# Photodiode_TIA_real_comp.net
KiCad netlist of a schematic drawn in Altium Designer
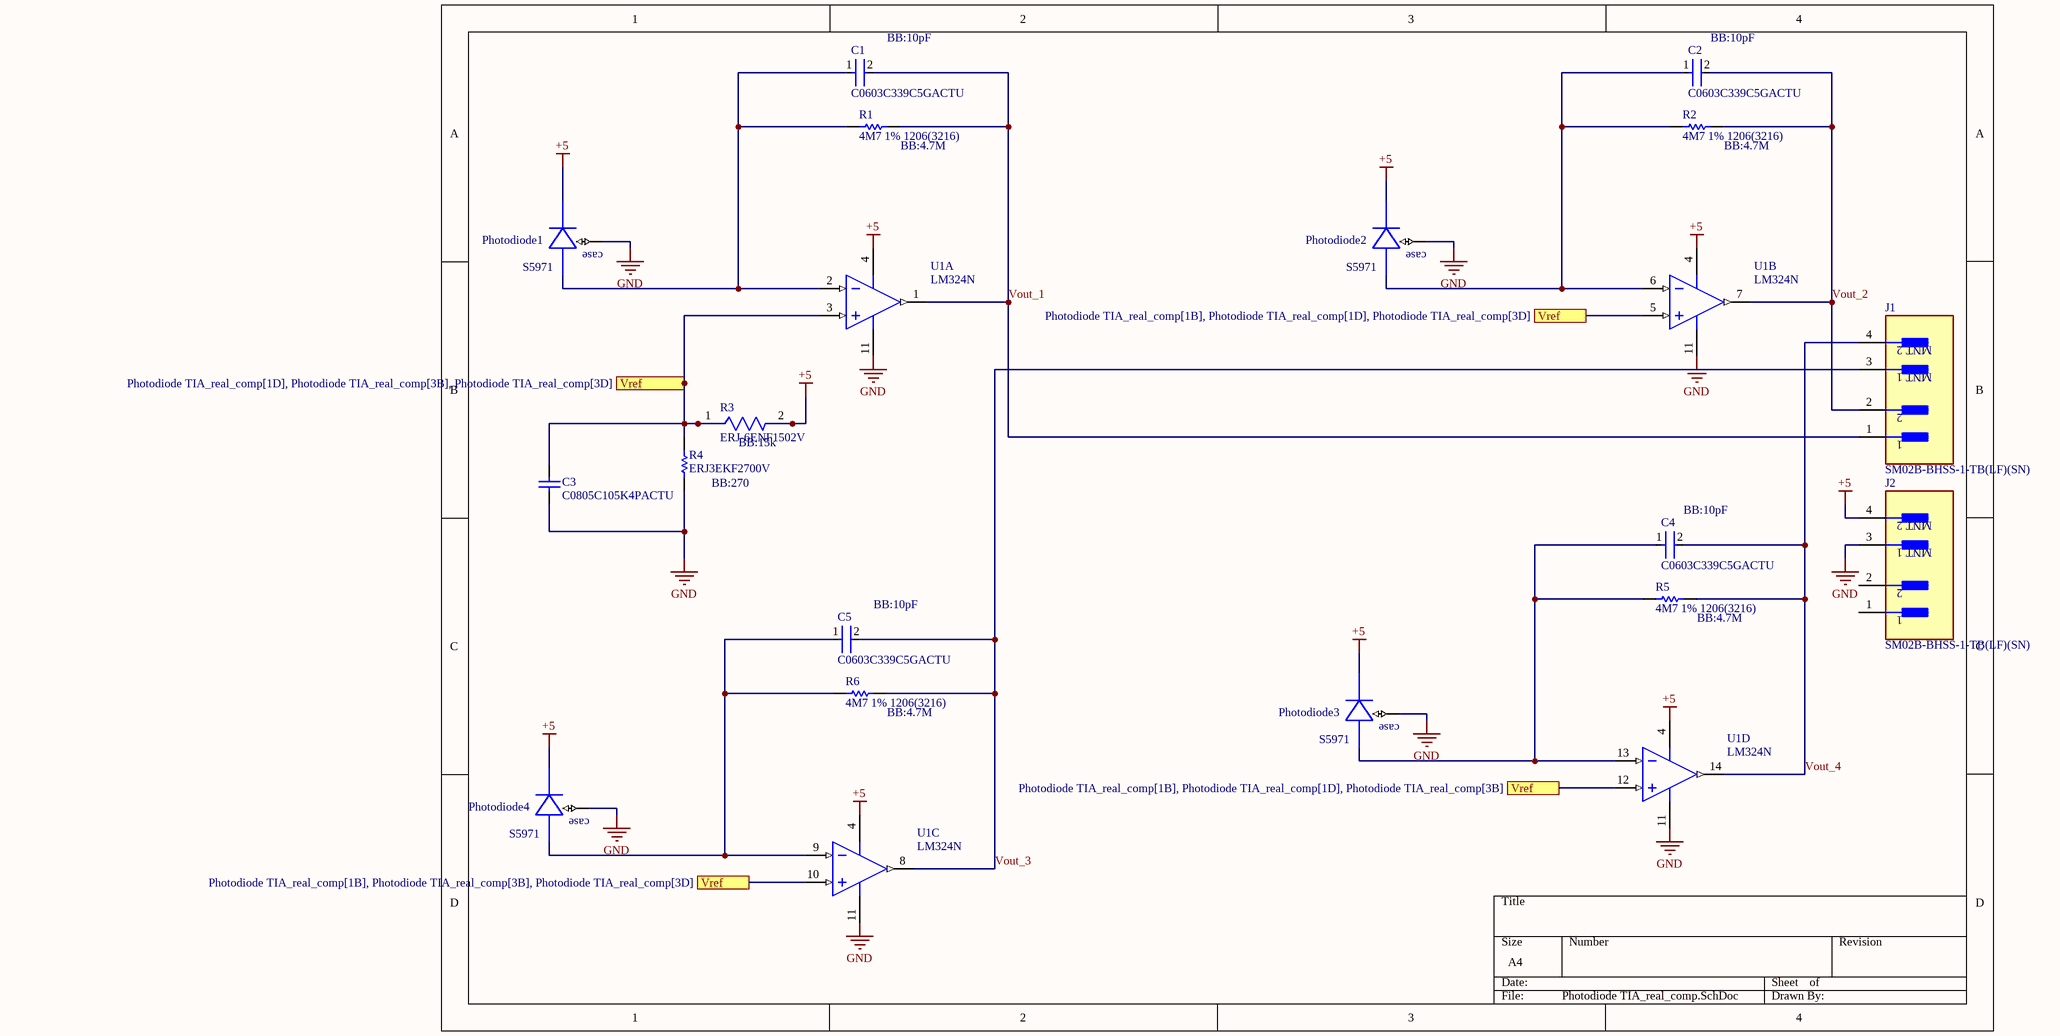
[diagram p0: Photodiode TIA_real_comp.SchDoc]

(export (version "E")
  (design (tool "Eeschema 10.0.6"))
  (components
    (comp (ref "C1")
      (value "C0603C339C5GACTU")
      (footprint "FP-C0603C-CF-MFG")
      (description "CAP CER 3.3PF 50V NP0 0603")
      (fields
        (field (name "TOLERANCE") "0.25 pF")
        (field (name "OCTOPART") "https://octopart.com/c0603c339c5gactu-kemet-3701205")
      )
      (libsource (lib "Altium Content Vault") (part "b4654b650e69147ec39a6b967a45e02"))
    )
    (comp (ref "C2")
      (value "C0603C339C5GACTU")
      (footprint "FP-C0603C-CF-MFG")
      (description "CAP CER 3.3PF 50V NP0 0603")
      (fields
        (field (name "TOLERANCE") "0.25 pF")
        (field (name "OCTOPART") "https://octopart.com/c0603c339c5gactu-kemet-3701205")
      )
      (libsource (lib "Altium Content Vault") (part "b4654b650e69147ec39a6b967a45e02"))
    )
    (comp (ref "C3")
      (value "C0805C105K4PACTU")
      (footprint "CAPC2013X145X50LL20T25")
      (fields (field (name "MANUFACTURER") "Kemet"))
      (libsource (lib "Altium Content Vault") (part "CAP"))
    )
    (comp (ref "C4")
      (value "C0603C339C5GACTU")
      (footprint "FP-C0603C-CF-MFG")
      (description "CAP CER 3.3PF 50V NP0 0603")
      (fields
        (field (name "TOLERANCE") "0.25 pF")
        (field (name "OCTOPART") "https://octopart.com/c0603c339c5gactu-kemet-3701205")
      )
      (libsource (lib "Altium Content Vault") (part "b4654b650e69147ec39a6b967a45e02"))
    )
    (comp (ref "C5")
      (value "C0603C339C5GACTU")
      (footprint "FP-C0603C-CF-MFG")
      (description "CAP CER 3.3PF 50V NP0 0603")
      (fields
        (field (name "TOLERANCE") "0.25 pF")
        (field (name "OCTOPART") "https://octopart.com/c0603c339c5gactu-kemet-3701205")
      )
      (libsource (lib "Altium Content Vault") (part "b4654b650e69147ec39a6b967a45e02"))
    )
    (comp (ref "J1")
      (value "SM02B-BHSS-1-TB(LF)(SN)")
      (footprint "FP-SM02B-BHSS-1-TB_LF_SN-MFG")
      (description "CONN HEADER SMD R/A 2POS 3.5MM")
      (fields
        (field (name "OCTOPART") "https://octopart.com/sm02b-bhss-1-tb%28lf%29%28sn%29-jst-655226")
        (field (name "MANUFACTURER") "JST")
      )
      (libsource (lib "Altium Content Vault") (part "56ec3178a87b3978bdc1b3682cd516a"))
    )
    (comp (ref "J2")
      (value "SM02B-BHSS-1-TB(LF)(SN)")
      (footprint "FP-SM02B-BHSS-1-TB_LF_SN-MFG")
      (description "CONN HEADER SMD R/A 2POS 3.5MM")
      (fields
        (field (name "OCTOPART") "https://octopart.com/sm02b-bhss-1-tb%28lf%29%28sn%29-jst-655226")
        (field (name "MANUFACTURER") "JST")
      )
      (libsource (lib "Altium Content Vault") (part "56ec3178a87b3978bdc1b3682cd516a"))
    )
    (comp (ref "Photodiode1")
      (value "S5971")
      (footprint "S5971-CASE")
      (description "Heat Shrink Tubing, Semi Rigid 0.250 _6.35mm_ 2 to 1 White")
      (fields (field (name "MF") "TE Connectivity"))
      (libsource (lib "S5971") (part "S5971"))
    )
    (comp (ref "Photodiode2")
      (value "S5971")
      (footprint "S5971-CASE")
      (description "Heat Shrink Tubing, Semi Rigid 0.250 _6.35mm_ 2 to 1 White")
      (fields (field (name "MF") "TE Connectivity"))
      (libsource (lib "S5971") (part "S5971"))
    )
    (comp (ref "Photodiode3")
      (value "S5971")
      (footprint "S5971-CASE")
      (description "Heat Shrink Tubing, Semi Rigid 0.250 _6.35mm_ 2 to 1 White")
      (fields (field (name "MF") "TE Connectivity"))
      (libsource (lib "S5971") (part "S5971"))
    )
    (comp (ref "Photodiode4")
      (value "S5971")
      (footprint "S5971-CASE")
      (description "Heat Shrink Tubing, Semi Rigid 0.250 _6.35mm_ 2 to 1 White")
      (fields (field (name "MF") "TE Connectivity"))
      (libsource (lib "S5971") (part "S5971"))
    )
    (comp (ref "R1")
      (value "4M7 1% 1206(3216)")
      (footprint "RESC1206(3216)_N")
      (description "4M7 0.25W 1% 1206 (3216 Metric)  SMD")
      (fields (field (name "TOLERANCE") "1 %") (field (name "POWER") "0.25 W"))
      (libsource (lib "Altium Content Vault") (part "RES"))
    )
    (comp (ref "R2")
      (value "4M7 1% 1206(3216)")
      (footprint "RESC1206(3216)_N")
      (description "4M7 0.25W 1% 1206 (3216 Metric)  SMD")
      (fields (field (name "TOLERANCE") "1 %") (field (name "POWER") "0.25 W"))
      (libsource (lib "Altium Content Vault") (part "RES"))
    )
    (comp (ref "R3")
      (value "ERJ-6ENF1502V")
      (footprint "FP-ERJ6EN-IPC_C")
      (description "RES SMD 15K OHM 1% 1/8W 0805")
      (fields (field (name "TOLERANCE") "1%"))
      (libsource (lib "Altium Content Vault") (part "8db39607336c341a927600551d01821"))
    )
    (comp (ref "R4")
      (value "ERJ3EKF2700V")
      (footprint "RESC1608X55X30LL15T15")
      (fields (field (name "MANUFACTURER") "Panasonic"))
      (libsource (lib "Altium Content Vault") (part "RES"))
    )
    (comp (ref "R5")
      (value "4M7 1% 1206(3216)")
      (footprint "RESC1206(3216)_N")
      (description "4M7 0.25W 1% 1206 (3216 Metric)  SMD")
      (fields (field (name "TOLERANCE") "1 %") (field (name "POWER") "0.25 W"))
      (libsource (lib "Altium Content Vault") (part "RES"))
    )
    (comp (ref "R6")
      (value "4M7 1% 1206(3216)")
      (footprint "RESC1206(3216)_N")
      (description "4M7 0.25W 1% 1206 (3216 Metric)  SMD")
      (fields (field (name "TOLERANCE") "1 %") (field (name "POWER") "0.25 W"))
      (libsource (lib "Altium Content Vault") (part "RES"))
    )
    (comp (ref "U1")
      (value "LM324N")
      (footprint "N0014A")
      (description "Low Power Quad Operational Amplifier, 14-pin MDIP")
      (fields (field (name "MANUFACTURER") "Texas Instruments"))
      (libsource (lib "Altium Content Vault") (part "AMP-OPA-LM124-14"))
    )
  )
  (nets
    (net (code "1") (name "+5") (class "Default")
      (node (ref "J2") (pin "4") (pinfunction "MNT_2_4") (pintype "passive"))
      (node (ref "Photodiode1") (pin "P$1") (pinfunction "CATHODE_P$1") (pintype "bidirectional"))
      (node (ref "Photodiode2") (pin "P$1") (pinfunction "CATHODE_P$1") (pintype "bidirectional"))
      (node (ref "Photodiode3") (pin "P$1") (pinfunction "CATHODE_P$1") (pintype "bidirectional"))
      (node (ref "Photodiode4") (pin "P$1") (pinfunction "CATHODE_P$1") (pintype "bidirectional"))
      (node (ref "R3") (pin "2") (pinfunction "2_2") (pintype "passive"))
      (node (ref "U1") (pin "4") (pinfunction "V+_4") (pintype "power_in"))
    )
    (net (code "2") (name "/Vout_1") (class "Default")
      (node (ref "C1") (pin "2") (pinfunction "2_2") (pintype "passive"))
      (node (ref "J1") (pin "1") (pinfunction "1_1") (pintype "passive"))
      (node (ref "R1") (pin "2") (pinfunction "2_2") (pintype "passive"))
      (node (ref "U1") (pin "1") (pinfunction "OUT1_1") (pintype "output"))
    )
    (net (code "3") (name "/Vout_2") (class "Default")
      (node (ref "C2") (pin "2") (pinfunction "2_2") (pintype "passive"))
      (node (ref "J1") (pin "2") (pinfunction "2_2") (pintype "passive"))
      (node (ref "R2") (pin "2") (pinfunction "2_2") (pintype "passive"))
      (node (ref "U1") (pin "7") (pinfunction "OUT2_7") (pintype "output"))
    )
    (net (code "4") (name "/Vout_3") (class "Default")
      (node (ref "C5") (pin "2") (pinfunction "2_2") (pintype "passive"))
      (node (ref "J1") (pin "3") (pinfunction "MNT_1_3") (pintype "passive"))
      (node (ref "R6") (pin "2") (pinfunction "2_2") (pintype "passive"))
      (node (ref "U1") (pin "8") (pinfunction "OUT3_8") (pintype "output"))
    )
    (net (code "5") (name "/Vout_4") (class "Default")
      (node (ref "C4") (pin "2") (pinfunction "2_2") (pintype "passive"))
      (node (ref "J1") (pin "4") (pinfunction "MNT_2_4") (pintype "passive"))
      (node (ref "R5") (pin "2") (pinfunction "2_2") (pintype "passive"))
      (node (ref "U1") (pin "14") (pinfunction "OUT4_14") (pintype "output"))
    )
    (net (code "6") (name "/Vref") (class "Default")
      (node (ref "C3") (pin "1") (pinfunction "1_1") (pintype "passive"))
      (node (ref "R3") (pin "1") (pinfunction "1_1") (pintype "passive"))
      (node (ref "R4") (pin "2") (pinfunction "2_2") (pintype "passive"))
      (node (ref "U1") (pin "10") (pinfunction "IN3+_10") (pintype "input"))
      (node (ref "U1") (pin "12") (pinfunction "IN4+_12") (pintype "input"))
      (node (ref "U1") (pin "3") (pinfunction "IN1+_3") (pintype "input"))
      (node (ref "U1") (pin "5") (pinfunction "IN2+_5") (pintype "input"))
    )
    (net (code "7") (name "GND") (class "Default")
      (node (ref "C3") (pin "2") (pinfunction "2_2") (pintype "passive"))
      (node (ref "J2") (pin "3") (pinfunction "MNT_1_3") (pintype "passive"))
      (node (ref "Photodiode1") (pin "P$2") (pinfunction "CASE_P$2") (pintype "bidirectional"))
      (node (ref "Photodiode2") (pin "P$2") (pinfunction "CASE_P$2") (pintype "bidirectional"))
      (node (ref "Photodiode3") (pin "P$2") (pinfunction "CASE_P$2") (pintype "bidirectional"))
      (node (ref "Photodiode4") (pin "P$2") (pinfunction "CASE_P$2") (pintype "bidirectional"))
      (node (ref "R4") (pin "1") (pinfunction "1_1") (pintype "passive"))
      (node (ref "U1") (pin "11") (pinfunction "GND_11") (pintype "power_in"))
    )
    (net (code "8") (name "Net-(Photodiode1-ANODE)") (class "Default")
      (node (ref "C1") (pin "1") (pinfunction "1_1") (pintype "passive"))
      (node (ref "Photodiode1") (pin "P$3") (pinfunction "ANODE_P$3") (pintype "bidirectional"))
      (node (ref "R1") (pin "1") (pinfunction "1_1") (pintype "passive"))
      (node (ref "U1") (pin "2") (pinfunction "IN1-_2") (pintype "input"))
    )
    (net (code "9") (name "Net-(Photodiode2-ANODE)") (class "Default")
      (node (ref "C2") (pin "1") (pinfunction "1_1") (pintype "passive"))
      (node (ref "Photodiode2") (pin "P$3") (pinfunction "ANODE_P$3") (pintype "bidirectional"))
      (node (ref "R2") (pin "1") (pinfunction "1_1") (pintype "passive"))
      (node (ref "U1") (pin "6") (pinfunction "IN2-_6") (pintype "input"))
    )
    (net (code "10") (name "Net-(Photodiode3-ANODE)") (class "Default")
      (node (ref "C4") (pin "1") (pinfunction "1_1") (pintype "passive"))
      (node (ref "Photodiode3") (pin "P$3") (pinfunction "ANODE_P$3") (pintype "bidirectional"))
      (node (ref "R5") (pin "1") (pinfunction "1_1") (pintype "passive"))
      (node (ref "U1") (pin "13") (pinfunction "IN4-_13") (pintype "input"))
    )
    (net (code "11") (name "Net-(Photodiode4-ANODE)") (class "Default")
      (node (ref "C5") (pin "1") (pinfunction "1_1") (pintype "passive"))
      (node (ref "Photodiode4") (pin "P$3") (pinfunction "ANODE_P$3") (pintype "bidirectional"))
      (node (ref "R6") (pin "1") (pinfunction "1_1") (pintype "passive"))
      (node (ref "U1") (pin "9") (pinfunction "IN3-_9") (pintype "input"))
    )
    (net (code "12") (name "unconnected-(J2-Pad1)") (class "Default")
      (node (ref "J2") (pin "1") (pinfunction "1_1") (pintype "passive"))
    )
    (net (code "13") (name "unconnected-(J2-Pad2)") (class "Default")
      (node (ref "J2") (pin "2") (pinfunction "2_2") (pintype "passive"))
    )
  )
)
